# tree_power.net
KiCad netlist of a schematic drawn in Altium Designer
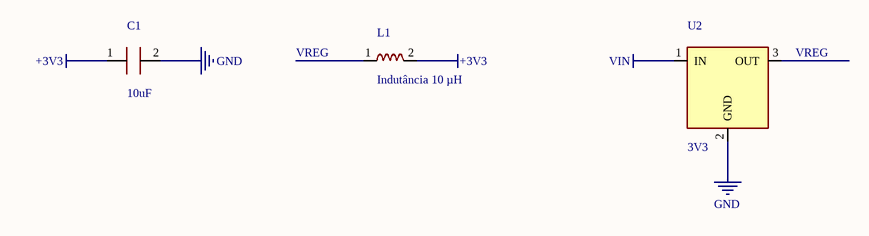
[diagram p0: tree_power.SchDoc]

(export (version "E")
  (design (tool "Eeschema 10.0.6"))
  (components
    (comp (ref "C1")
      (value "10uF")
      (footprint "FenoliteTree:C0603")
      (fields (field (name "MPN") "X-1"))
      (libsource (lib "tree") (part "Capacitor"))
    )
    (comp (ref "L1")
      (value "Indutância 10 µH")
      (footprint "FenoliteTree:L0805")
      (libsource (lib "tree") (part "Inductor"))
    )
    (comp (ref "U2")
      (value "3V3")
      (footprint "FenoliteTree:SOT223")
      (libsource (lib "tree") (part "Linear_Regulator"))
    )
  )
  (nets
    (net (code "1") (name "+3V3") (class "Default")
      (node (ref "C1") (pin "1") (pinfunction "A_1") (pintype "passive"))
      (node (ref "L1") (pin "2") (pinfunction "B_2") (pintype "passive"))
    )
    (net (code "2") (name "/VREG") (class "Default")
      (node (ref "L1") (pin "1") (pinfunction "A_1") (pintype "passive"))
      (node (ref "U2") (pin "3") (pinfunction "OUT_3") (pintype "power_in"))
    )
    (net (code "3") (name "GND") (class "Default")
      (node (ref "C1") (pin "2") (pinfunction "B_2") (pintype "passive"))
      (node (ref "U2") (pin "2") (pinfunction "GND_2") (pintype "power_in"))
    )
    (net (code "4") (name "VIN") (class "Default")
      (node (ref "U2") (pin "1") (pinfunction "IN_1") (pintype "power_in"))
    )
  )
)
